# Underwater_vehicle-V3_0.net
KiCad netlist of a schematic drawn in Altium Designer
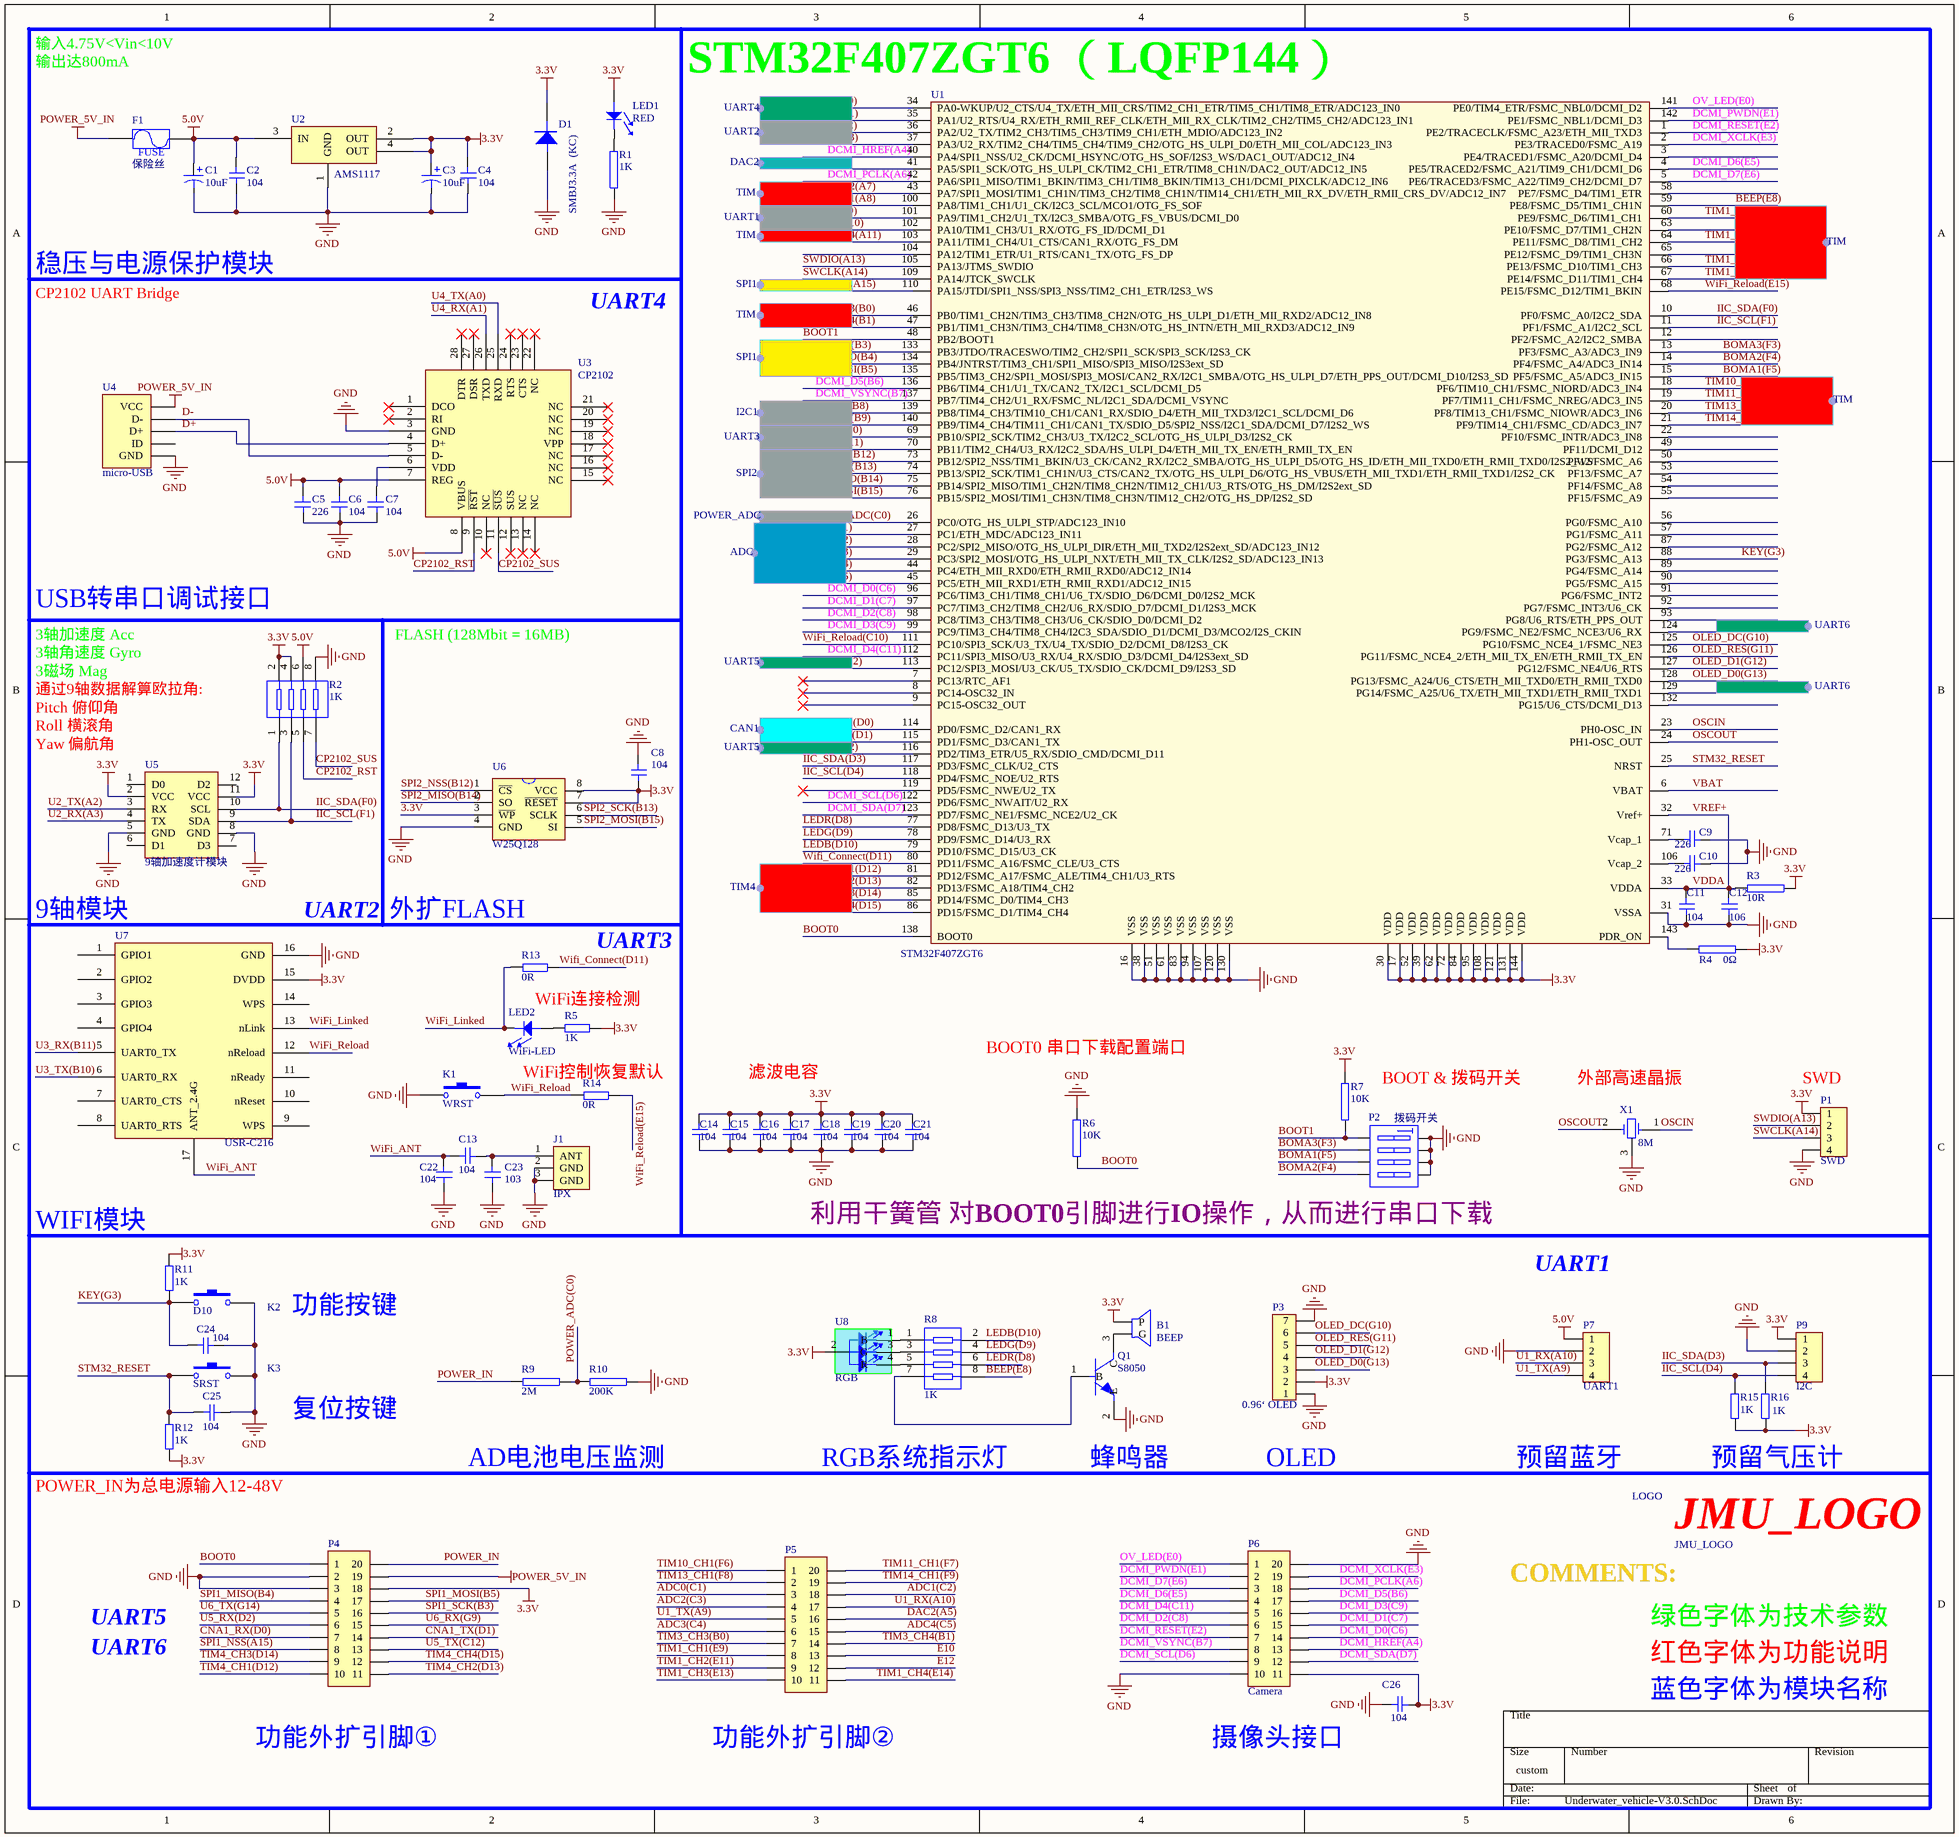
[diagram p0: Underwater_vehicle-V3.0.SchDoc]

(export (version "E")
  (design (tool "Eeschema 10.0.6"))
  (components
    (comp (ref "B1") (value "BEEP") (footprint "BUZZER") (libsource (lib "EXPLORER") (part "BEEP")))
    (comp (ref "C1")
      (value "10uF")
      (footprint "TAJ-A")
      (description "极性贴片电容")
      (libsource (lib "集大电协1.1.0") (part "Pol Cap"))
    )
    (comp (ref "C2")
      (value "104")
      (footprint "0805C")
      (description "无极贴片电容")
      (libsource (lib "集大电协1.1.0") (part "Cap1"))
    )
    (comp (ref "C3")
      (value "10uF")
      (footprint "TAJ-A")
      (description "极性贴片电容")
      (libsource (lib "集大电协1.1.0") (part "Pol Cap"))
    )
    (comp (ref "C4")
      (value "104")
      (footprint "0805C")
      (description "无极贴片电容")
      (libsource (lib "集大电协1.1.0") (part "Cap1"))
    )
    (comp (ref "C5")
      (value "226")
      (footprint "0805C")
      (description "无极贴片电容")
      (libsource (lib "集大电协1.1.0") (part "Cap1"))
    )
    (comp (ref "C6")
      (value "104")
      (footprint "0805C")
      (description "无极贴片电容")
      (libsource (lib "集大电协1.1.0") (part "Cap1"))
    )
    (comp (ref "C7")
      (value "104")
      (footprint "0805C")
      (description "无极贴片电容")
      (libsource (lib "集大电协1.1.0") (part "Cap1"))
    )
    (comp (ref "C8")
      (value "104")
      (footprint "0805C")
      (description "无极贴片电容")
      (libsource (lib "集大电协1.1.0") (part "Cap1"))
    )
    (comp (ref "C9") (value "226") (footprint "0805C") (libsource (lib "窝牛器件封装") (part "C1")))
    (comp (ref "C10") (value "226") (footprint "0805C") (libsource (lib "窝牛器件封装") (part "C1")))
    (comp (ref "C11") (value "104") (footprint "0805C") (libsource (lib "窝牛器件封装") (part "C1")))
    (comp (ref "C12") (value "106") (footprint "0805C") (libsource (lib "窝牛器件封装") (part "C1")))
    (comp (ref "C13")
      (value "104")
      (footprint "0805C")
      (description "无极贴片电容")
      (libsource (lib "集大电协1.1.2") (part "Cap1"))
    )
    (comp (ref "C14") (value "104") (footprint "0805C") (libsource (lib "窝牛器件封装") (part "C1")))
    (comp (ref "C15") (value "104") (footprint "0805C") (libsource (lib "窝牛器件封装") (part "C1")))
    (comp (ref "C16") (value "104") (footprint "0805C") (libsource (lib "窝牛器件封装") (part "C1")))
    (comp (ref "C17") (value "104") (footprint "0805C") (libsource (lib "窝牛器件封装") (part "C1")))
    (comp (ref "C18") (value "104") (footprint "0805C") (libsource (lib "窝牛器件封装") (part "C1")))
    (comp (ref "C19") (value "104") (footprint "0805C") (libsource (lib "窝牛器件封装") (part "C1")))
    (comp (ref "C20") (value "104") (footprint "0805C") (libsource (lib "窝牛器件封装") (part "C1")))
    (comp (ref "C21") (value "104") (footprint "0805C") (libsource (lib "窝牛器件封装") (part "C1")))
    (comp (ref "C22")
      (value "104")
      (footprint "0805C")
      (description "无极贴片电容")
      (libsource (lib "集大电协1.1.2") (part "Cap1"))
    )
    (comp (ref "C23")
      (value "103")
      (footprint "0805C")
      (description "无极贴片电容")
      (libsource (lib "集大电协1.1.2") (part "Cap1"))
    )
    (comp (ref "C24") (value "104") (footprint "0805C") (libsource (lib "窝牛器件封装") (part "C1")))
    (comp (ref "C25") (value "104") (footprint "0805C") (libsource (lib "窝牛器件封装") (part "C1")))
    (comp (ref "C26")
      (value "104")
      (footprint "0805C")
      (description "无极贴片电容")
      (libsource (lib "集大电协1.1.5") (part "Cap1"))
    )
    (comp (ref "D1")
      (value "SMBJ3.3A  (KC)")
      (footprint "SMBJ")
      (description "二极管")
      (libsource (lib "集大电协1.1.0") (part "Diode"))
    )
    (comp (ref "F1") (value "保险丝") (footprint "1812") (libsource (lib "集大电协1.1.2") (part "Fuse")))
    (comp (ref "J1") (value "IPX") (footprint "IPX天线底座") (libsource (lib "集大电协1.1.2") (part "IPX天线座")))
    (comp (ref "K1")
      (value "WRST")
      (footprint "贴片按键")
      (description "轻触开关")
      (libsource (lib "集大电协1.1.2") (part "轻触按键"))
    )
    (comp (ref "K2") (value "D10") (footprint "贴片按键") (libsource (lib "窝牛器件封装") (part "Key(两脚贴片)")))
    (comp (ref "K3") (value "SRST") (footprint "贴片按键") (libsource (lib "窝牛器件封装") (part "Key(两脚贴片)")))
    (comp (ref "LED1")
      (value "RED")
      (footprint "0805LED(RED)")
      (description "发光二极管")
      (libsource (lib "集大电协1.1.2") (part "LED"))
    )
    (comp (ref "LED2")
      (value "WiFi-LED")
      (footprint "0805LED(GREEN)")
      (description "发光二极管")
      (libsource (lib "集大电协1.1.2") (part "LED"))
    )
    (comp (ref "LOGO")
      (value "JMU_LOGO")
      (footprint "JMU_LOGO(1.35cm)")
      (description "LOGO")
      (libsource (lib "集大电协1.1.5") (part "JMU_LOGO"))
    )
    (comp (ref "P1")
      (value "SWD")
      (footprint "Header 4")
      (description "排针")
      (libsource (lib "集大电协1.1.0") (part "Header 4"))
    )
    (comp (ref "P2")
      (value "拨码开关")
      (footprint "拨码开关(4位贴片)")
      (description "4位拨码开关")
      (libsource (lib "集大电协1.1.2") (part "拨码开关4"))
    )
    (comp (ref "P3")
      (value "0.96‘ OLED")
      (footprint "Header 7")
      (description "排针")
      (libsource (lib "集大电协1.1.5") (part "Header 7"))
    )
    (comp (ref "P4") (value "~") (footprint "Header 10X2") (libsource (lib "集大电协1.1.2") (part "Header 10X2")))
    (comp (ref "P5") (value "~") (footprint "Header 10X2") (libsource (lib "集大电协1.1.2") (part "Header 10X2")))
    (comp (ref "P6")
      (value "Camera")
      (footprint "Header 10X2")
      (libsource (lib "集大电协1.1.2") (part "Header 10X2"))
    )
    (comp (ref "P7")
      (value "UART1")
      (footprint "Header 4(排母)")
      (description "排针")
      (libsource (lib "集大电协1.1.5") (part "Header 4"))
    )
    (comp (ref "P9")
      (value "I2C")
      (footprint "Header 4(排母)")
      (description "排针")
      (libsource (lib "集大电协1.1.5") (part "Header 4"))
    )
    (comp (ref "Q1")
      (value "S8050")
      (footprint "SOT-23")
      (description "NPN三极管")
      (libsource (lib "集大电协1.1.2") (part "NPN"))
    )
    (comp (ref "R1") (value "1K") (footprint "0805R") (libsource (lib "窝牛器件封装") (part "R1")))
    (comp (ref "R2")
      (value "1K")
      (footprint "排阻(4位贴片)")
      (description "排阻")
      (libsource (lib "集大电协1.1.2") (part "Res-4"))
    )
    (comp (ref "R3") (value "10R") (footprint "0805R") (libsource (lib "窝牛器件封装") (part "R1")))
    (comp (ref "R4") (value "0Ω") (footprint "0805R") (libsource (lib "窝牛器件封装") (part "R1")))
    (comp (ref "R5")
      (value "1K")
      (footprint "0805R")
      (description "电阻")
      (libsource (lib "集大电协1.1.2") (part "Res"))
    )
    (comp (ref "R6") (value "10K") (footprint "0805R") (libsource (lib "窝牛器件封装") (part "R1")))
    (comp (ref "R7") (value "10K") (footprint "0805R") (libsource (lib "窝牛器件封装") (part "R1")))
    (comp (ref "R8")
      (value "1K")
      (footprint "排阻(4位贴片)")
      (description "排阻")
      (libsource (lib "集大电协1.1.2") (part "Res-4"))
    )
    (comp (ref "R9") (value "2M") (footprint "0805R") (libsource (lib "窝牛器件封装") (part "R1")))
    (comp (ref "R10") (value "200K") (footprint "0805R") (libsource (lib "窝牛器件封装") (part "R1")))
    (comp (ref "R11")
      (value "1K")
      (footprint "0805R")
      (description "电阻")
      (libsource (lib "集大电协1.1.5") (part "Res"))
    )
    (comp (ref "R12")
      (value "1K")
      (footprint "0805R")
      (description "电阻")
      (libsource (lib "集大电协1.1.5") (part "Res"))
    )
    (comp (ref "R13")
      (value "0R")
      (footprint "0805R")
      (description "电阻")
      (libsource (lib "集大电协1.1.5") (part "Res"))
    )
    (comp (ref "R14")
      (value "0R")
      (footprint "0805R")
      (description "电阻")
      (libsource (lib "集大电协1.1.5") (part "Res"))
    )
    (comp (ref "R15")
      (value "1K")
      (footprint "0805R")
      (description "电阻")
      (libsource (lib "集大电协1.2") (part "Res"))
    )
    (comp (ref "R16")
      (value "1K")
      (footprint "0805R")
      (description "电阻")
      (libsource (lib "集大电协1.2") (part "Res"))
    )
    (comp (ref "U1")
      (value "STM32F407ZGT6")
      (footprint "LQFP-144")
      (libsource (lib "窝牛器件封装") (part "STM32F407ZET6"))
    )
    (comp (ref "U2")
      (value "AMS1117")
      (footprint "SOT-223")
      (description "电源芯片")
      (libsource (lib "集大电协1.1.0") (part "AMS1117-3.3V/5.0V"))
    )
    (comp (ref "U3")
      (value "CP2102")
      (footprint "QFN-28")
      (description "USB转串口芯片")
      (libsource (lib "集大电协1.1.0") (part "CP2102"))
    )
    (comp (ref "U4")
      (value "micro-USB")
      (footprint "Micro-USB (兼容牛角)")
      (description "USB接口")
      (libsource (lib "集大电协1.1.2") (part "micro-USB"))
    )
    (comp (ref "U5") (value "9轴加速度计模块") (footprint "9轴加速度计") (libsource (lib "窝牛器件封装") (part "9轴加速度计")))
    (comp (ref "U6")
      (value "W25Q128")
      (footprint "SOW-8")
      (description "FLASH芯片")
      (libsource (lib "集大电协1.1.0") (part "W25Q128"))
    )
    (comp (ref "U7")
      (value "USR-C216")
      (footprint "USR-C216")
      (libsource (lib "集大电协1.1.2") (part "USR-C216"))
    )
    (comp (ref "U8") (value "RGB") (footprint "RGB-3528") (libsource (lib "集大电协1.1.2") (part "RGB")))
    (comp (ref "X1") (value "8M") (footprint "三脚贴片8M晶振") (libsource (lib "集大电协1.1.2") (part "XTAL三脚贴片晶振")))
  )
  (nets
    (net (code "2") (name "/ADC0(C1)") (class "Default")
      (node (ref "P5") (pin "3") (pinfunction "3_3") (pintype "passive"))
      (node (ref "U1") (pin "27") (pinfunction "PC1/ETH_MDC/ADC123_IN11_27") (pintype "passive"))
    )
    (net (code "3") (name "/ADC1(C2)") (class "Default")
      (node (ref "P5") (pin "18") (pinfunction "18_18") (pintype "passive"))
      (node (ref "U1") (pin "28") (pinfunction "PC2/SPI2_MISO/OTG_HS_ULPI_DIR/ETH_MII_TXD2/I2S2ext_SD/ADC123_IN12_28") (pintype "passive"))
    )
    (net (code "4") (name "/ADC2(C3)") (class "Default")
      (node (ref "P5") (pin "4") (pinfunction "4_4") (pintype "passive"))
      (node (ref "U1") (pin "29") (pinfunction "PC3/SPI2_MOSI/OTG_HS_ULPI_NXT/ETH_MII_TX_CLK/I2S2_SD/ADC123_IN13_29") (pintype "passive"))
    )
    (net (code "5") (name "/ADC3(C4)") (class "Default")
      (node (ref "P5") (pin "6") (pinfunction "6_6") (pintype "passive"))
      (node (ref "U1") (pin "44") (pinfunction "PC4/ETH_MII_RXD0/ETH_RMII_RXD0/ADC12_IN14_44") (pintype "passive"))
    )
    (net (code "6") (name "/ADC4(C5)") (class "Default")
      (node (ref "P5") (pin "15") (pinfunction "15_15") (pintype "passive"))
      (node (ref "U1") (pin "45") (pinfunction "PC5/ETH_MII_RXD1/ETH_RMII_RXD1/ADC12_IN15_45") (pintype "passive"))
    )
    (net (code "7") (name "/BEEP(E8)") (class "Default")
      (node (ref "R8") (pin "8") (pinfunction "8_8") (pintype "passive"))
      (node (ref "U1") (pin "59") (pinfunction "PE8/FSMC_D5/TIM1_CH1N_59") (pintype "passive"))
    )
    (net (code "8") (name "/BOMA1(F5)") (class "Default")
      (node (ref "P2") (pin "3") (pinfunction "A3_3") (pintype "passive"))
      (node (ref "U1") (pin "15") (pinfunction "PF5/FSMC_A5/ADC3_IN15_15") (pintype "passive"))
    )
    (net (code "9") (name "/BOMA2(F4)") (class "Default")
      (node (ref "P2") (pin "4") (pinfunction "A4_4") (pintype "passive"))
      (node (ref "U1") (pin "14") (pinfunction "PF4/FSMC_A4/ADC3_IN14_14") (pintype "passive"))
    )
    (net (code "10") (name "/BOMA3(F3)") (class "Default")
      (node (ref "P2") (pin "2") (pinfunction "A2_2") (pintype "passive"))
      (node (ref "U1") (pin "13") (pinfunction "PF3/FSMC_A3/ADC3_IN9_13") (pintype "passive"))
    )
    (net (code "11") (name "/BOOT0") (class "Default")
      (node (ref "P4") (pin "1") (pinfunction "1_1") (pintype "passive"))
      (node (ref "R6") (pin "1") (pinfunction "1_1") (pintype "passive"))
      (node (ref "U1") (pin "138") (pinfunction "BOOT0_138") (pintype "passive"))
    )
    (net (code "12") (name "/BOOT1") (class "Default")
      (node (ref "P2") (pin "1") (pinfunction "A1_1") (pintype "passive"))
      (node (ref "R7") (pin "1") (pinfunction "1_1") (pintype "passive"))
      (node (ref "U1") (pin "48") (pinfunction "PB2/BOOT1_48") (pintype "passive"))
    )
    (net (code "13") (name "/CNA1_RX(D0)") (class "Default")
      (node (ref "P4") (pin "7") (pinfunction "7_7") (pintype "passive"))
      (node (ref "U1") (pin "114") (pinfunction "PD0/FSMC_D2/CAN1_RX_114") (pintype "passive"))
    )
    (net (code "14") (name "/CNA1_TX(D1)") (class "Default")
      (node (ref "P4") (pin "14") (pinfunction "14_14") (pintype "passive"))
      (node (ref "U1") (pin "115") (pinfunction "PD1/FSMC_D3/CAN1_TX_115") (pintype "passive"))
    )
    (net (code "15") (name "/CP2102_RST") (class "Default")
      (node (ref "R2") (pin "5") (pinfunction "5_5") (pintype "passive"))
      (node (ref "U3") (pin "9") (pinfunction "~{RST}_9") (pintype "passive"))
    )
    (net (code "16") (name "/CP2102_SUS") (class "Default")
      (node (ref "R2") (pin "7") (pinfunction "7_7") (pintype "passive"))
      (node (ref "U3") (pin "11") (pinfunction "~{SUS}_11") (pintype "passive"))
    )
    (net (code "17") (name "/D+") (class "Default")
      (node (ref "U3") (pin "4") (pinfunction "D+_4") (pintype "passive"))
      (node (ref "U4") (pin "3") (pinfunction "D+_3") (pintype "power_in"))
    )
    (net (code "18") (name "/D-") (class "Default")
      (node (ref "U3") (pin "5") (pinfunction "D-_5") (pintype "passive"))
      (node (ref "U4") (pin "2") (pinfunction "D-_2") (pintype "power_in"))
    )
    (net (code "19") (name "/DAC2(A5)") (class "Default")
      (node (ref "P5") (pin "16") (pinfunction "16_16") (pintype "passive"))
      (node (ref "U1") (pin "41") (pinfunction "PA5/SPI1_SCK/OTG_HS_ULPI_CK/TIM2_CH1_ETR/TIM8_CH1N/DAC2_OUT/ADC12_IN5_41") (pintype "passive"))
    )
    (net (code "20") (name "/DCMI_D0(C6)") (class "Default")
      (node (ref "P6") (pin "14") (pinfunction "14_14") (pintype "passive"))
      (node (ref "U1") (pin "96") (pinfunction "PC6/TIM3_CH1/TIM8_CH1/U6_TX/SDIO_D6/DCMI_D0/I2S2_MCK_96") (pintype "passive"))
    )
    (net (code "21") (name "/DCMI_D1(C7)") (class "Default")
      (node (ref "P6") (pin "15") (pinfunction "15_15") (pintype "passive"))
      (node (ref "U1") (pin "97") (pinfunction "PC7/TIM3_CH2/TIM8_CH2/U6_RX/SDIO_D7/DCMI_D1/I2S3_MCK_97") (pintype "passive"))
    )
    (net (code "22") (name "/DCMI_D2(C8)") (class "Default")
      (node (ref "P6") (pin "6") (pinfunction "6_6") (pintype "passive"))
      (node (ref "U1") (pin "98") (pinfunction "PC8/TIM3_CH3/TIM8_CH3/U6_CK/SDIO_D0/DCMI_D2_98") (pintype "passive"))
    )
    (net (code "23") (name "/DCMI_D3(C9)") (class "Default")
      (node (ref "P6") (pin "16") (pinfunction "16_16") (pintype "passive"))
      (node (ref "U1") (pin "99") (pinfunction "PC9/TIM3_CH4/TIM8_CH4/I2C3_SDA/SDIO_D1/DCMI_D3/MCO2/I2S_CKIN_99") (pintype "passive"))
    )
    (net (code "24") (name "/DCMI_D4(C11)") (class "Default")
      (node (ref "P6") (pin "5") (pinfunction "5_5") (pintype "passive"))
      (node (ref "U1") (pin "112") (pinfunction "PC11/SPI3_MISO/U3_RX/U4_RX/SDIO_D3/DCMI_D4/I2S3ext_SD_112") (pintype "passive"))
    )
    (net (code "25") (name "/DCMI_D5(B6)") (class "Default")
      (node (ref "P6") (pin "17") (pinfunction "17_17") (pintype "passive"))
      (node (ref "U1") (pin "136") (pinfunction "PB6/TIM4_CH1/U1_TX/CAN2_TX/I2C1_SCL/DCMI_D5_136") (pintype "passive"))
    )
    (net (code "26") (name "/DCMI_D6(E5)") (class "Default")
      (node (ref "P6") (pin "4") (pinfunction "4_4") (pintype "passive"))
      (node (ref "U1") (pin "4") (pinfunction "PE5/TRACED2/FSMC_A21/TIM9_CH1/DCMI_D6_4") (pintype "passive"))
    )
    (net (code "27") (name "/DCMI_D7(E6)") (class "Default")
      (node (ref "P6") (pin "3") (pinfunction "3_3") (pintype "passive"))
      (node (ref "U1") (pin "5") (pinfunction "PE6/TRACED3/FSMC_A22/TIM9_CH2/DCMI_D7_5") (pintype "passive"))
    )
    (net (code "28") (name "/DCMI_HREF(A4)") (class "Default")
      (node (ref "P6") (pin "13") (pinfunction "13_13") (pintype "passive"))
      (node (ref "U1") (pin "40") (pinfunction "PA4/SPI1_NSS/U2_CK/DCMI_HSYNC/OTG_HS_SOF/I2S3_WS/DAC1_OUT/ADC12_IN4_40") (pintype "passive"))
    )
    (net (code "29") (name "/DCMI_PCLK(A6)") (class "Default")
      (node (ref "P6") (pin "18") (pinfunction "18_18") (pintype "passive"))
      (node (ref "U1") (pin "42") (pinfunction "PA6/SPI1_MISO/TIM1_BKIN/TIM3_CH1/TIM8_BKIN/TIM13_CH1/DCMI_PIXCLK/ADC12_IN6_42") (pintype "passive"))
    )
    (net (code "30") (name "/DCMI_PWDN(E1)") (class "Default")
      (node (ref "P6") (pin "2") (pinfunction "2_2") (pintype "passive"))
      (node (ref "U1") (pin "142") (pinfunction "PE1/FSMC_NBL1/DCMI_D3_142") (pintype "passive"))
    )
    (net (code "31") (name "/DCMI_RESET(E2)") (class "Default")
      (node (ref "P6") (pin "7") (pinfunction "7_7") (pintype "passive"))
      (node (ref "U1") (pin "1") (pinfunction "PE2/TRACECLK/FSMC_A23/ETH_MII_TXD3_1") (pintype "passive"))
    )
    (net (code "32") (name "/DCMI_SCL(D6)") (class "Default")
      (node (ref "P6") (pin "9") (pinfunction "9_9") (pintype "passive"))
      (node (ref "U1") (pin "122") (pinfunction "PD6/FSMC_NWAIT/U2_RX_122") (pintype "passive"))
    )
    (net (code "33") (name "/DCMI_SDA(D7)") (class "Default")
      (node (ref "P6") (pin "12") (pinfunction "12_12") (pintype "passive"))
      (node (ref "U1") (pin "123") (pinfunction "PD7/FSMC_NE1/FSMC_NCE2/U2_CK_123") (pintype "passive"))
    )
    (net (code "34") (name "/DCMI_VSYNC(B7)") (class "Default")
      (node (ref "P6") (pin "8") (pinfunction "8_8") (pintype "passive"))
      (node (ref "U1") (pin "137") (pinfunction "PB7/TIM4_CH2/U1_RX/FSMC_NL/I2C1_SDA/DCMI_VSYNC_137") (pintype "passive"))
    )
    (net (code "35") (name "/DCMI_XCLK(E3)") (class "Default")
      (node (ref "P6") (pin "19") (pinfunction "19_19") (pintype "passive"))
      (node (ref "U1") (pin "2") (pinfunction "PE3/TRACED0/FSMC_A19_2") (pintype "passive"))
    )
    (net (code "36") (name "/E10") (class "Default")
      (node (ref "P5") (pin "13") (pinfunction "13_13") (pintype "passive"))
      (node (ref "U1") (pin "63") (pinfunction "PE10/FSMC_D7/TIM1_CH2N_63") (pintype "passive"))
    )
    (net (code "37") (name "/E12") (class "Default")
      (node (ref "P5") (pin "12") (pinfunction "12_12") (pintype "passive"))
      (node (ref "U1") (pin "65") (pinfunction "PE12/FSMC_D9/TIM1_CH3N_65") (pintype "passive"))
    )
    (net (code "38") (name "/IIC1_SCL(B8)") (class "Default")
      (node (ref "U1") (pin "139") (pinfunction "PB8/TIM4_CH3/TIM10_CH1/CAN1_RX/SDIO_D4/ETH_MII_TXD3/I2C1_SCL/DCMI_D6_139") (pintype "passive"))
    )
    (net (code "39") (name "/IIC1_SDA(B9)") (class "Default")
      (node (ref "U1") (pin "140") (pinfunction "PB9/TIM4_CH4/TIM11_CH1/CAN1_TX/SDIO_D5/SPI2_NSS/I2C1_SDA/DCMI_D7/I2S2_WS_140") (pintype "passive"))
    )
    (net (code "40") (name "/IIC_SCL(D4)") (class "Default")
      (node (ref "P9") (pin "4") (pinfunction "4_4") (pintype "passive"))
      (node (ref "R15") (pin "2") (pinfunction "2_2") (pintype "passive"))
      (node (ref "U1") (pin "118") (pinfunction "PD4/FSMC_NOE/U2_RTS_118") (pintype "passive"))
    )
    (net (code "41") (name "/IIC_SCL(F1)") (class "Default")
      (node (ref "R2") (pin "3") (pinfunction "3_3") (pintype "passive"))
      (node (ref "U1") (pin "11") (pinfunction "PF1/FSMC_A1/I2C2_SCL_11") (pintype "passive"))
      (node (ref "U5") (pin "9") (pinfunction "SDA_9") (pintype "passive"))
    )
    (net (code "42") (name "/IIC_SDA(D3)") (class "Default")
      (node (ref "P9") (pin "3") (pinfunction "3_3") (pintype "passive"))
      (node (ref "R16") (pin "2") (pinfunction "2_2") (pintype "passive"))
      (node (ref "U1") (pin "117") (pinfunction "PD3/FSMC_CLK/U2_CTS_117") (pintype "passive"))
    )
    (net (code "43") (name "/IIC_SDA(F0)") (class "Default")
      (node (ref "R2") (pin "1") (pinfunction "1_1") (pintype "passive"))
      (node (ref "U1") (pin "10") (pinfunction "PF0/FSMC_A0/I2C2_SDA_10") (pintype "passive"))
      (node (ref "U5") (pin "10") (pinfunction "SCL_10") (pintype "passive"))
    )
    (net (code "44") (name "/KEY(G3)") (class "Default")
      (node (ref "C24") (pin "1") (pinfunction "1_1") (pintype "passive"))
      (node (ref "K2") (pin "1") (pinfunction "1_1") (pintype "passive"))
      (node (ref "R11") (pin "1") (pinfunction "1_1") (pintype "passive"))
      (node (ref "U1") (pin "88") (pinfunction "PG3/FSMC_A13_88") (pintype "passive"))
    )
    (net (code "45") (name "/LEDB(D10)") (class "Default")
      (node (ref "R8") (pin "2") (pinfunction "2_2") (pintype "passive"))
      (node (ref "U1") (pin "79") (pinfunction "PD10/FSMC_D15/U3_CK_79") (pintype "passive"))
    )
    (net (code "46") (name "/LEDG(D9)") (class "Default")
      (node (ref "R8") (pin "4") (pinfunction "4_4") (pintype "passive"))
      (node (ref "U1") (pin "78") (pinfunction "PD9/FSMC_D14/U3_RX_78") (pintype "passive"))
    )
    (net (code "47") (name "/LEDR(D8)") (class "Default")
      (node (ref "R8") (pin "6") (pinfunction "6_6") (pintype "passive"))
      (node (ref "U1") (pin "77") (pinfunction "PD8/FSMC_D13/U3_TX_77") (pintype "passive"))
    )
    (net (code "48") (name "/OLED_D0(G13)") (class "Default")
      (node (ref "P3") (pin "3") (pinfunction "3_3") (pintype "passive"))
      (node (ref "U1") (pin "128") (pinfunction "PG13/FSMC_A24/U6_CTS/ETH_MII_TXD0/ETH_RMII_TXD0_128") (pintype "passive"))
    )
    (net (code "49") (name "/OLED_D1(G12)") (class "Default")
      (node (ref "P3") (pin "4") (pinfunction "4_4") (pintype "passive"))
      (node (ref "U1") (pin "127") (pinfunction "PG12/FSMC_NE4/U6_RTS_127") (pintype "passive"))
    )
    (net (code "50") (name "/OLED_DC(G10)") (class "Default")
      (node (ref "P3") (pin "6") (pinfunction "6_6") (pintype "passive"))
      (node (ref "U1") (pin "125") (pinfunction "PG10/FSMC_NCE4_1/FSMC_NE3_125") (pintype "passive"))
    )
    (net (code "51") (name "/OLED_RES(G11)") (class "Default")
      (node (ref "P3") (pin "5") (pinfunction "5_5") (pintype "passive"))
      (node (ref "U1") (pin "126") (pinfunction "PG11/FSMC_NCE4_2/ETH_MII_TX_EN/ETH_RMII_TX_EN_126") (pintype "passive"))
    )
    (net (code "52") (name "/OSCIN") (class "Default")
      (node (ref "U1") (pin "23") (pinfunction "PH0-OSC_IN_23") (pintype "passive"))
      (node (ref "X1") (pin "1") (pinfunction "1_1") (pintype "passive"))
    )
    (net (code "53") (name "/OSCOUT") (class "Default")
      (node (ref "U1") (pin "24") (pinfunction "PH1-OSC_OUT_24") (pintype "passive"))
      (node (ref "X1") (pin "2") (pinfunction "2_2") (pintype "passive"))
    )
    (net (code "54") (name "/OV_LED(E0)") (class "Default")
      (node (ref "P6") (pin "1") (pinfunction "1_1") (pintype "passive"))
      (node (ref "U1") (pin "141") (pinfunction "PE0/TIM4_ETR/FSMC_NBL0/DCMI_D2_141") (pintype "passive"))
    )
    (net (code "55") (name "/POWER_ADC(C0)") (class "Default")
      (node (ref "R10") (pin "1") (pinfunction "1_1") (pintype "passive"))
      (node (ref "R9") (pin "2") (pinfunction "2_2") (pintype "passive"))
      (node (ref "U1") (pin "26") (pinfunction "PC0/OTG_HS_ULPI_STP/ADC123_IN10_26") (pintype "passive"))
    )
    (net (code "56") (name "/POWER_IN") (class "Default")
      (node (ref "P4") (pin "20") (pinfunction "20_20") (pintype "passive"))
      (node (ref "R9") (pin "1") (pinfunction "1_1") (pintype "passive"))
    )
    (net (code "57") (name "/SPI1_MISO(B4)") (class "Default")
      (node (ref "P4") (pin "4") (pinfunction "4_4") (pintype "passive"))
      (node (ref "U1") (pin "134") (pinfunction "PB4/JNTRST/TIM3_CH1/SPI1_MISO/SPI3_MISO/I2S3ext_SD_134") (pintype "passive"))
    )
    (net (code "58") (name "/SPI1_MOSI(B5)") (class "Default")
      (node (ref "P4") (pin "17") (pinfunction "17_17") (pintype "passive"))
      (node (ref "U1") (pin "135") (pinfunction "PB5/TIM3_CH2/SPI1_MOSI/SPI3_MOSI/CAN2_RX/I2C1_SMBA/OTG_HS_ULPI_D7/ETH_PPS_OUT/DCMI_D10/I2S3_SD_135") (pintype "passive"))
    )
    (net (code "59") (name "/SPI1_NSS(A15)") (class "Default")
      (node (ref "P4") (pin "8") (pinfunction "8_8") (pintype "passive"))
      (node (ref "U1") (pin "110") (pinfunction "PA15/JTDI/SPI1_NSS/SPI3_NSS/TIM2_CH1_ETR/I2S3_WS_110") (pintype "passive"))
    )
    (net (code "60") (name "/SPI1_SCK(B3)") (class "Default")
      (node (ref "P4") (pin "16") (pinfunction "16_16") (pintype "passive"))
      (node (ref "U1") (pin "133") (pinfunction "PB3/JTDO/TRACESWO/TIM2_CH2/SPI1_SCK/SPI3_SCK/I2S3_CK_133") (pintype "passive"))
    )
    (net (code "61") (name "/SPI2_MISO(B14)") (class "Default")
      (node (ref "U1") (pin "75") (pinfunction "PB14/SPI2_MISO/TIM1_CH2N/TIM8_CH2N/TIM12_CH1/U3_RTS/OTG_HS_DM/I2S2ext_SD_75") (pintype "passive"))
      (node (ref "U6") (pin "2") (pinfunction "SO_2") (pintype "passive"))
    )
    (net (code "62") (name "/SPI2_MOSI(B15)") (class "Default")
      (node (ref "U1") (pin "76") (pinfunction "PB15/SPI2_MOSI/TIM1_CH3N/TIM8_CH3N/TIM12_CH2/OTG_HS_DP/I2S2_SD_76") (pintype "passive"))
      (node (ref "U6") (pin "5") (pinfunction "SI_5") (pintype "passive"))
    )
    (net (code "63") (name "/SPI2_NSS(B12)") (class "Default")
      (node (ref "U1") (pin "73") (pinfunction "PB12/SPI2_NSS/TIM1_BKIN/U3_CK/CAN2_RX/I2C2_SMBA/OTG_HS_ULPI_D5/OTG_HS_ID/ETH_MII_TXD0/ETH_RMII_TXD0/I2S2_WS_73") (pintype "passive"))
      (node (ref "U6") (pin "1") (pinfunction "~{CS}_1") (pintype "passive"))
    )
    (net (code "64") (name "/SPI2_SCK(B13)") (class "Default")
      (node (ref "U1") (pin "74") (pinfunction "PB13/SPI2_SCK/TIM1_CH1N/U3_CTS/CAN2_TX/OTG_HS_ULPI_D6/OTG_HS_VBUS/ETH_MII_TXD1/ETH_RMII_TXD1/I2S2_CK_74") (pintype "passive"))
      (node (ref "U6") (pin "6") (pinfunction "SCLK_6") (pintype "passive"))
    )
    (net (code "65") (name "/STM32_RESET") (class "Default")
      (node (ref "C25") (pin "1") (pinfunction "1_1") (pintype "passive"))
      (node (ref "K3") (pin "1") (pinfunction "1_1") (pintype "passive"))
      (node (ref "R12") (pin "2") (pinfunction "2_2") (pintype "passive"))
      (node (ref "U1") (pin "25") (pinfunction "NRST_25") (pintype "passive"))
    )
    (net (code "66") (name "/SWCLK(A14)") (class "Default")
      (node (ref "P1") (pin "3") (pinfunction "3_3") (pintype "passive"))
      (node (ref "U1") (pin "109") (pinfunction "PA14/JTCK_SWCLK_109") (pintype "passive"))
    )
    (net (code "67") (name "/SWDIO(A13)") (class "Default")
      (node (ref "P1") (pin "2") (pinfunction "2_2") (pintype "passive"))
      (node (ref "U1") (pin "105") (pinfunction "PA13/JTMS_SWDIO_105") (pintype "passive"))
    )
    (net (code "68") (name "/TIM1_CH1(A8)") (class "Default")
      (node (ref "U1") (pin "100") (pinfunction "PA8/TIM1_CH1/U1_CK/I2C3_SCL/MCO1/OTG_FS_SOF_100") (pintype "passive"))
    )
    (net (code "69") (name "/TIM1_CH1(E9)") (class "Default")
      (node (ref "P5") (pin "8") (pinfunction "8_8") (pintype "passive"))
      (node (ref "U1") (pin "60") (pinfunction "PE9/FSMC_D6/TIM1_CH1_60") (pintype "passive"))
    )
    (net (code "70") (name "/TIM1_CH2(E11)") (class "Default")
      (node (ref "P5") (pin "9") (pinfunction "9_9") (pintype "passive"))
      (node (ref "U1") (pin "64") (pinfunction "PE11/FSMC_D8/TIM1_CH2_64") (pintype "passive"))
    )
    (net (code "71") (name "/TIM1_CH3(E13)") (class "Default")
      (node (ref "P5") (pin "10") (pinfunction "10_10") (pintype "passive"))
      (node (ref "U1") (pin "66") (pinfunction "PE13/FSMC_D10/TIM1_CH3_66") (pintype "passive"))
    )
    (net (code "72") (name "/TIM1_CH4(A11)") (class "Default")
      (node (ref "U1") (pin "103") (pinfunction "PA11/TIM1_CH4/U1_CTS/CAN1_RX/OTG_FS_DM_103") (pintype "passive"))
    )
    (net (code "73") (name "/TIM1_CH4(E14)") (class "Default")
      (node (ref "P5") (pin "11") (pinfunction "11_11") (pintype "passive"))
      (node (ref "U1") (pin "67") (pinfunction "PE14/FSMC_D11/TIM1_CH4_67") (pintype "passive"))
    )
    (net (code "74") (name "/TIM3_CH2(A7)") (class "Default")
      (node (ref "U1") (pin "43") (pinfunction "PA7/SPI1_MOSI/TIM1_CH1N/TIM3_CH2/TIM8_CH1N/TIM14_CH1/ETH_MII_RX_DV/ETH_RMII_CRS_DV/ADC12_IN7_43") (pintype "passive"))
    )
    (net (code "75") (name "/TIM3_CH3(B0)") (class "Default")
      (node (ref "P5") (pin "7") (pinfunction "7_7") (pintype "passive"))
      (node (ref "U1") (pin "46") (pinfunction "PB0/TIM1_CH2N/TIM3_CH3/TIM8_CH2N/OTG_HS_ULPI_D1/ETH_MII_RXD2/ADC12_IN8_46") (pintype "passive"))
    )
    (net (code "76") (name "/TIM3_CH4(B1)") (class "Default")
      (node (ref "P5") (pin "14") (pinfunction "14_14") (pintype "passive"))
      (node (ref "U1") (pin "47") (pinfunction "PB1/TIM1_CH3N/TIM3_CH4/TIM8_CH3N/OTG_HS_INTN/ETH_MII_RXD3/ADC12_IN9_47") (pintype "passive"))
    )
    (net (code "77") (name "/TIM4_CH1(D12)") (class "Default")
      (node (ref "P4") (pin "10") (pinfunction "10_10") (pintype "passive"))
      (node (ref "U1") (pin "81") (pinfunction "PD12/FSMC_A17/FSMC_ALE/TIM4_CH1/U3_RTS_81") (pintype "passive"))
    )
    (net (code "78") (name "/TIM4_CH2(D13)") (class "Default")
      (node (ref "P4") (pin "11") (pinfunction "11_11") (pintype "passive"))
      (node (ref "U1") (pin "82") (pinfunction "PD13/FSMC_A18/TIM4_CH2_82") (pintype "passive"))
    )
    (net (code "79") (name "/TIM4_CH3(D14)") (class "Default")
      (node (ref "P4") (pin "9") (pinfunction "9_9") (pintype "passive"))
      (node (ref "U1") (pin "85") (pinfunction "PD14/FSMC_D0/TIM4_CH3_85") (pintype "passive"))
    )
    (net (code "80") (name "/TIM4_CH4(D15)") (class "Default")
      (node (ref "P4") (pin "12") (pinfunction "12_12") (pintype "passive"))
      (node (ref "U1") (pin "86") (pinfunction "PD15/FSMC_D1/TIM4_CH4_86") (pintype "passive"))
    )
    (net (code "81") (name "/TIM10_CH1(F6)") (class "Default")
      (node (ref "P5") (pin "1") (pinfunction "1_1") (pintype "passive"))
      (node (ref "U1") (pin "18") (pinfunction "PF6/TIM10_CH1/FSMC_NIORD/ADC3_IN4_18") (pintype "passive"))
    )
    (net (code "82") (name "/TIM11_CH1(F7)") (class "Default")
      (node (ref "P5") (pin "20") (pinfunction "20_20") (pintype "passive"))
      (node (ref "U1") (pin "19") (pinfunction "PF7/TIM11_CH1/FSMC_NREG/ADC3_IN5_19") (pintype "passive"))
    )
    (net (code "83") (name "/TIM13_CH1(F8)") (class "Default")
      (node (ref "P5") (pin "2") (pinfunction "2_2") (pintype "passive"))
      (node (ref "U1") (pin "20") (pinfunction "PF8/TIM13_CH1/FSMC_NIOWR/ADC3_IN6_20") (pintype "passive"))
    )
    (net (code "84") (name "/TIM14_CH1(F9)") (class "Default")
      (node (ref "P5") (pin "19") (pinfunction "19_19") (pintype "passive"))
      (node (ref "U1") (pin "21") (pinfunction "PF9/TIM14_CH1/FSMC_CD/ADC3_IN7_21") (pintype "passive"))
    )
    (net (code "85") (name "/U1_RX(A10)") (class "Default")
      (node (ref "P5") (pin "17") (pinfunction "17_17") (pintype "passive"))
      (node (ref "P7") (pin "3") (pinfunction "3_3") (pintype "passive"))
      (node (ref "U1") (pin "102") (pinfunction "PA10/TIM1_CH3/U1_RX/OTG_FS_ID/DCMI_D1_102") (pintype "passive"))
    )
    (net (code "86") (name "/U1_TX(A9)") (class "Default")
      (node (ref "P5") (pin "5") (pinfunction "5_5") (pintype "passive"))
      (node (ref "P7") (pin "4") (pinfunction "4_4") (pintype "passive"))
      (node (ref "U1") (pin "101") (pinfunction "PA9/TIM1_CH2/U1_TX/I2C3_SMBA/OTG_FS_VBUS/DCMI_D0_101") (pintype "passive"))
    )
    (net (code "87") (name "/U2_RX(A3)") (class "Default")
      (node (ref "U1") (pin "37") (pinfunction "PA3/U2_RX/TIM2_CH4/TIM5_CH4/TIM9_CH2/OTG_HS_ULPI_D0/ETH_MII_COL/ADC123_IN3_37") (pintype "passive"))
      (node (ref "U5") (pin "4") (pinfunction "TX_4") (pintype "passive"))
    )
    (net (code "88") (name "/U2_TX(A2)") (class "Default")
      (node (ref "U1") (pin "36") (pinfunction "PA2/U2_TX/TIM2_CH3/TIM5_CH3/TIM9_CH1/ETH_MDIO/ADC123_IN2_36") (pintype "passive"))
      (node (ref "U5") (pin "3") (pinfunction "RX_3") (pintype "passive"))
    )
    (net (code "89") (name "/U3_RX(B11)") (class "Default")
      (node (ref "U1") (pin "70") (pinfunction "PB11/TIM2_CH4/U3_RX/I2C2_SDA/HS_ULPI_D4/ETH_MII_TX_EN/ETH_RMII_TX_EN_70") (pintype "passive"))
      (node (ref "U7") (pin "5") (pinfunction "UART0_TX_5") (pintype "passive"))
    )
    (net (code "90") (name "/U3_TX(B10)") (class "Default")
      (node (ref "U1") (pin "69") (pinfunction "PB10/SPI2_SCK/TIM2_CH3/U3_TX/I2C2_SCL/OTG_HS_ULPI_D3/I2S2_CK_69") (pintype "passive"))
      (node (ref "U7") (pin "6") (pinfunction "UART0_RX_6") (pintype "passive"))
    )
    (net (code "91") (name "/U4_RX(A1)") (class "Default")
      (node (ref "U1") (pin "35") (pinfunction "PA1/U2_RTS/U4_RX/ETH_RMII_REF_CLK/ETH_MII_RX_CLK/TIM2_CH2/TIM5_CH2/ADC123_IN1_35") (pintype "passive"))
      (node (ref "U3") (pin "26") (pinfunction "TXD_26") (pintype "passive"))
    )
    (net (code "92") (name "/U4_TX(A0)") (class "Default")
      (node (ref "U1") (pin "34") (pinfunction "PA0-WKUP/U2_CTS/U4_TX/ETH_MII_CRS/TIM2_CH1_ETR/TIM5_CH1/TIM8_ETR/ADC123_IN0_34") (pintype "passive"))
      (node (ref "U3") (pin "25") (pinfunction "RXD_25") (pintype "passive"))
    )
    (net (code "93") (name "/U5_RX(D2)") (class "Default")
      (node (ref "P4") (pin "6") (pinfunction "6_6") (pintype "passive"))
      (node (ref "U1") (pin "116") (pinfunction "PD2/TIM3_ETR/U5_RX/SDIO_CMD/DCMI_D11_116") (pintype "passive"))
    )
    (net (code "94") (name "/U5_TX(C12)") (class "Default")
      (node (ref "P4") (pin "13") (pinfunction "13_13") (pintype "passive"))
      (node (ref "U1") (pin "113") (pinfunction "PC12/SPI3_MOSI/U3_CK/U5_TX/SDIO_CK/DCMI_D9/I2S3_SD_113") (pintype "passive"))
    )
    (net (code "95") (name "/U6_RX(G9)") (class "Default")
      (node (ref "P4") (pin "15") (pinfunction "15_15") (pintype "passive"))
      (node (ref "U1") (pin "124") (pinfunction "PG9/FSMC_NE2/FSMC_NCE3/U6_RX_124") (pintype "passive"))
    )
    (net (code "96") (name "/U6_TX(G14)") (class "Default")
      (node (ref "P4") (pin "5") (pinfunction "5_5") (pintype "passive"))
      (node (ref "U1") (pin "129") (pinfunction "PG14/FSMC_A25/U6_TX/ETH_MII_TXD1/ETH_RMII_TXD1_129") (pintype "passive"))
    )
    (net (code "97") (name "/VBAT") (class "Default")
      (node (ref "U1") (pin "6") (pinfunction "VBAT_6") (pintype "passive"))
    )
    (net (code "98") (name "/VDDA") (class "Default")
      (node (ref "C11") (pin "2") (pinfunction "2_2") (pintype "passive"))
      (node (ref "C12") (pin "2") (pinfunction "2_2") (pintype "passive"))
      (node (ref "R3") (pin "1") (pinfunction "1_1") (pintype "passive"))
      (node (ref "U1") (pin "32") (pinfunction "Vref+_32") (pintype "passive"))
      (node (ref "U1") (pin "33") (pinfunction "VDDA_33") (pintype "passive"))
    )
    (net (code "99") (name "/WiFi_ANT") (class "Default")
      (node (ref "C13") (pin "2") (pinfunction "2_2") (pintype "passive"))
      (node (ref "C22") (pin "2") (pinfunction "2_2") (pintype "passive"))
      (node (ref "U7") (pin "17") (pinfunction "ANT_2.4G_17") (pintype "passive"))
    )
    (net (code "100") (name "/WiFi_Linked") (class "Default")
      (node (ref "LED2") (pin "2") (pinfunction "2_2") (pintype "passive"))
      (node (ref "R13") (pin "1") (pinfunction "1_1") (pintype "passive"))
      (node (ref "U7") (pin "13") (pinfunction "nLink_13") (pintype "passive"))
    )
    (net (code "101") (name "/WiFi_Reload") (class "Default")
      (node (ref "K1") (pin "2") (pinfunction "2_2") (pintype "passive"))
      (node (ref "R14") (pin "1") (pinfunction "1_1") (pintype "passive"))
      (node (ref "U7") (pin "12") (pinfunction "nReload_12") (pintype "passive"))
    )
    (net (code "102") (name "/WiFi_Reload(C10)") (class "Default")
      (node (ref "U1") (pin "111") (pinfunction "PC10/SPI3_SCK/U3_TX/U4_TX/SDIO_D2/DCMI_D8/I2S3_CK_111") (pintype "passive"))
    )
    (net (code "103") (name "/WiFi_Reload(E15)") (class "Default")
      (node (ref "R14") (pin "2") (pinfunction "2_2") (pintype "passive"))
      (node (ref "U1") (pin "68") (pinfunction "PE15/FSMC_D12/TIM1_BKIN_68") (pintype "passive"))
    )
    (net (code "104") (name "/Wifi_Connect(D11)") (class "Default")
      (node (ref "R13") (pin "2") (pinfunction "2_2") (pintype "passive"))
      (node (ref "U1") (pin "80") (pinfunction "PD11/FSMC_A16/FSMC_CLE/U3_CTS_80") (pintype "passive"))
    )
    (net (code "105") (name "3.3V") (class "Default")
      (node (ref "B1") (pin "1") (pinfunction "P_1") (pintype "passive"))
      (node (ref "C14") (pin "2") (pinfunction "2_2") (pintype "passive"))
      (node (ref "C15") (pin "2") (pinfunction "2_2") (pintype "passive"))
      (node (ref "C16") (pin "2") (pinfunction "2_2") (pintype "passive"))
      (node (ref "C17") (pin "2") (pinfunction "2_2") (pintype "passive"))
      (node (ref "C18") (pin "2") (pinfunction "2_2") (pintype "passive"))
      (node (ref "C19") (pin "2") (pinfunction "2_2") (pintype "passive"))
      (node (ref "C20") (pin "2") (pinfunction "2_2") (pintype "passive"))
      (node (ref "C21") (pin "2") (pinfunction "2_2") (pintype "passive"))
      (node (ref "C26") (pin "1") (pinfunction "1_1") (pintype "passive"))
      (node (ref "C3") (pin "1") (pinfunction "1_1") (pintype "passive"))
      (node (ref "C4") (pin "2") (pinfunction "2_2") (pintype "passive"))
      (node (ref "C8") (pin "1") (pinfunction "1_1") (pintype "passive"))
      (node (ref "D1") (pin "2") (pinfunction "2_2") (pintype "passive"))
      (node (ref "LED1") (pin "1") (pintype "passive"))
      (node (ref "P1") (pin "1") (pinfunction "1_1") (pintype "passive"))
      (node (ref "P3") (pin "2") (pinfunction "2_2") (pintype "passive"))
      (node (ref "P4") (pin "18") (pinfunction "18_18") (pintype "passive"))
      (node (ref "P6") (pin "11") (pinfunction "11_11") (pintype "passive"))
      (node (ref "P9") (pin "1") (pinfunction "1_1") (pintype "passive"))
      (node (ref "R11") (pin "2") (pinfunction "2_2") (pintype "passive"))
      (node (ref "R12") (pin "1") (pinfunction "1_1") (pintype "passive"))
      (node (ref "R15") (pin "1") (pinfunction "1_1") (pintype "passive"))
      (node (ref "R16") (pin "1") (pinfunction "1_1") (pintype "passive"))
      (node (ref "R2") (pin "2") (pinfunction "2_2") (pintype "passive"))
      (node (ref "R2") (pin "4") (pinfunction "4_4") (pintype "passive"))
      (node (ref "R3") (pin "2") (pinfunction "2_2") (pintype "passive"))
      (node (ref "R4") (pin "2") (pinfunction "2_2") (pintype "passive"))
      (node (ref "R5") (pin "1") (pinfunction "1_1") (pintype "passive"))
      (node (ref "R7") (pin "2") (pinfunction "2_2") (pintype "passive"))
      (node (ref "U1") (pin "108") (pinfunction "VDD_108") (pintype "passive"))
      (node (ref "U1") (pin "121") (pinfunction "VDD_121") (pintype "passive"))
      (node (ref "U1") (pin "131") (pinfunction "VDD_131") (pintype "passive"))
      (node (ref "U1") (pin "144") (pinfunction "VDD_144") (pintype "passive"))
      (node (ref "U1") (pin "17") (pinfunction "VDD_17") (pintype "passive"))
      (node (ref "U1") (pin "30") (pinfunction "VDD_30") (pintype "passive"))
      (node (ref "U1") (pin "39") (pinfunction "VDD_39") (pintype "passive"))
      (node (ref "U1") (pin "52") (pinfunction "VDD_52") (pintype "passive"))
      (node (ref "U1") (pin "62") (pinfunction "VDD_62") (pintype "passive"))
      (node (ref "U1") (pin "72") (pinfunction "VDD_72") (pintype "passive"))
      (node (ref "U1") (pin "84") (pinfunction "VDD_84") (pintype "passive"))
      (node (ref "U1") (pin "95") (pinfunction "VDD_95") (pintype "passive"))
      (node (ref "U2") (pin "2") (pinfunction "OUT_2") (pintype "passive"))
      (node (ref "U2") (pin "4") (pinfunction "OUT_4") (pintype "passive"))
      (node (ref "U5") (pin "11") (pinfunction "VCC_11") (pintype "passive"))
      (node (ref "U5") (pin "2") (pinfunction "VCC_2") (pintype "passive"))
      (node (ref "U6") (pin "3") (pinfunction "~{WP}_3") (pintype "passive"))
      (node (ref "U6") (pin "7") (pinfunction "~{RESET}_7") (pintype "passive"))
      (node (ref "U6") (pin "8") (pinfunction "VCC_8") (pintype "passive"))
      (node (ref "U7") (pin "15") (pinfunction "DVDD_15") (pintype "passive"))
      (node (ref "U8") (pin "2") (pinfunction "2_2") (pintype "passive"))
    )
    (net (code "106") (name "5.0V") (class "Default")
      (node (ref "C1") (pin "1") (pinfunction "1_1") (pintype "passive"))
      (node (ref "C2") (pin "2") (pinfunction "2_2") (pintype "passive"))
      (node (ref "C5") (pin "1") (pinfunction "1_1") (pintype "passive"))
      (node (ref "C6") (pin "1") (pinfunction "1_1") (pintype "passive"))
      (node (ref "F1") (pin "2") (pinfunction "2_2") (pintype "passive"))
      (node (ref "P7") (pin "1") (pinfunction "1_1") (pintype "passive"))
      (node (ref "R2") (pin "6") (pinfunction "6_6") (pintype "passive"))
      (node (ref "U2") (pin "3") (pinfunction "IN_3") (pintype "passive"))
      (node (ref "U3") (pin "7") (pinfunction "REG_7") (pintype "passive"))
      (node (ref "U3") (pin "8") (pinfunction "VBUS_8") (pintype "passive"))
    )
    (net (code "107") (name "GND") (class "Default")
      (node (ref "C1") (pin "2") (pinfunction "2_2") (pintype "passive"))
      (node (ref "C10") (pin "1") (pinfunction "1_1") (pintype "passive"))
      (node (ref "C11") (pin "1") (pinfunction "1_1") (pintype "passive"))
      (node (ref "C12") (pin "1") (pinfunction "1_1") (pintype "passive"))
      (node (ref "C14") (pin "1") (pinfunction "1_1") (pintype "passive"))
      (node (ref "C15") (pin "1") (pinfunction "1_1") (pintype "passive"))
      (node (ref "C16") (pin "1") (pinfunction "1_1") (pintype "passive"))
      (node (ref "C17") (pin "1") (pinfunction "1_1") (pintype "passive"))
      (node (ref "C18") (pin "1") (pinfunction "1_1") (pintype "passive"))
      (node (ref "C19") (pin "1") (pinfunction "1_1") (pintype "passive"))
      (node (ref "C2") (pin "1") (pinfunction "1_1") (pintype "passive"))
      (node (ref "C20") (pin "1") (pinfunction "1_1") (pintype "passive"))
      (node (ref "C21") (pin "1") (pinfunction "1_1") (pintype "passive"))
      (node (ref "C22") (pin "1") (pinfunction "1_1") (pintype "passive"))
      (node (ref "C23") (pin "1") (pinfunction "1_1") (pintype "passive"))
      (node (ref "C24") (pin "2") (pinfunction "2_2") (pintype "passive"))
      (node (ref "C25") (pin "2") (pinfunction "2_2") (pintype "passive"))
      (node (ref "C26") (pin "2") (pinfunction "2_2") (pintype "passive"))
      (node (ref "C3") (pin "2") (pinfunction "2_2") (pintype "passive"))
      (node (ref "C4") (pin "1") (pinfunction "1_1") (pintype "passive"))
      (node (ref "C5") (pin "2") (pinfunction "2_2") (pintype "passive"))
      (node (ref "C6") (pin "2") (pinfunction "2_2") (pintype "passive"))
      (node (ref "C7") (pin "2") (pinfunction "2_2") (pintype "passive"))
      (node (ref "C8") (pin "2") (pinfunction "2_2") (pintype "passive"))
      (node (ref "C9") (pin "1") (pinfunction "1_1") (pintype "passive"))
      (node (ref "D1") (pin "1") (pintype "passive"))
      (node (ref "J1") (pin "2") (pinfunction "GND_2") (pintype "passive"))
      (node (ref "J1") (pin "3") (pinfunction "GND_3") (pintype "passive"))
      (node (ref "K1") (pin "1") (pinfunction "1_1") (pintype "passive"))
      (node (ref "K2") (pin "2") (pinfunction "2_2") (pintype "passive"))
      (node (ref "K3") (pin "2") (pinfunction "2_2") (pintype "passive"))
      (node (ref "P1") (pin "4") (pinfunction "4_4") (pintype "passive"))
      (node (ref "P2") (pin "5") (pinfunction "B4_5") (pintype "passive"))
      (node (ref "P2") (pin "6") (pinfunction "B3_6") (pintype "passive"))
      (node (ref "P2") (pin "7") (pinfunction "B2_7") (pintype "passive"))
      (node (ref "P2") (pin "8") (pinfunction "B1_8") (pintype "passive"))
      (node (ref "P3") (pin "1") (pinfunction "1_1") (pintype "passive"))
      (node (ref "P3") (pin "7") (pinfunction "7_7") (pintype "passive"))
      (node (ref "P4") (pin "2") (pinfunction "2_2") (pintype "passive"))
      (node (ref "P4") (pin "3") (pinfunction "3_3") (pintype "passive"))
      (node (ref "P6") (pin "10") (pinfunction "10_10") (pintype "passive"))
      (node (ref "P6") (pin "20") (pinfunction "20_20") (pintype "passive"))
      (node (ref "P7") (pin "2") (pinfunction "2_2") (pintype "passive"))
      (node (ref "P9") (pin "2") (pinfunction "2_2") (pintype "passive"))
      (node (ref "Q1") (pin "2") (pinfunction "E_2") (pintype "passive"))
      (node (ref "R1") (pin "1") (pinfunction "1_1") (pintype "passive"))
      (node (ref "R10") (pin "2") (pinfunction "2_2") (pintype "passive"))
      (node (ref "R2") (pin "8") (pinfunction "8_8") (pintype "passive"))
      (node (ref "R6") (pin "2") (pinfunction "2_2") (pintype "passive"))
      (node (ref "U1") (pin "107") (pinfunction "VSS_107") (pintype "passive"))
      (node (ref "U1") (pin "120") (pinfunction "VSS_120") (pintype "passive"))
      (node (ref "U1") (pin "130") (pinfunction "VSS_130") (pintype "passive"))
      (node (ref "U1") (pin "16") (pinfunction "VSS_16") (pintype "passive"))
      (node (ref "U1") (pin "31") (pinfunction "VSSA_31") (pintype "passive"))
      (node (ref "U1") (pin "38") (pinfunction "VSS_38") (pintype "passive"))
      (node (ref "U1") (pin "51") (pinfunction "VSS_51") (pintype "passive"))
      (node (ref "U1") (pin "61") (pinfunction "VSS_61") (pintype "passive"))
      (node (ref "U1") (pin "83") (pinfunction "VSS_83") (pintype "passive"))
      (node (ref "U1") (pin "94") (pinfunction "VSS_94") (pintype "passive"))
      (node (ref "U2") (pin "1") (pinfunction "GND_1") (pintype "passive"))
      (node (ref "U3") (pin "3") (pinfunction "GND_3") (pintype "passive"))
      (node (ref "U4") (pin "5") (pinfunction "GND_5") (pintype "power_in"))
      (node (ref "U5") (pin "5") (pinfunction "GND_5") (pintype "passive"))
      (node (ref "U5") (pin "8") (pinfunction "GND_8") (pintype "passive"))
      (node (ref "U6") (pin "4") (pinfunction "GND_4") (pintype "passive"))
      (node (ref "U7") (pin "16") (pinfunction "GND_16") (pintype "passive"))
      (node (ref "X1") (pin "3") (pinfunction "3_3") (pintype "passive"))
    )
    (net (code "108") (name "Net-(B1-G)") (class "Default")
      (node (ref "B1") (pin "2") (pinfunction "G_2") (pintype "passive"))
      (node (ref "Q1") (pin "3") (pinfunction "C_3") (pintype "passive"))
    )
    (net (code "109") (name "Net-(J1-ANT)") (class "Default")
      (node (ref "C13") (pin "1") (pinfunction "1_1") (pintype "passive"))
      (node (ref "C23") (pin "2") (pinfunction "2_2") (pintype "passive"))
      (node (ref "J1") (pin "1") (pinfunction "ANT_1") (pintype "passive"))
    )
    (net (code "110") (name "Net-(LED1-Pad2)") (class "Default")
      (node (ref "LED1") (pin "2") (pinfunction "2_2") (pintype "passive"))
      (node (ref "R1") (pin "2") (pinfunction "2_2") (pintype "passive"))
    )
    (net (code "111") (name "Net-(LED2-Pad1)") (class "Default")
      (node (ref "LED2") (pin "1") (pintype "passive"))
      (node (ref "R5") (pin "2") (pinfunction "2_2") (pintype "passive"))
    )
    (net (code "112") (name "Net-(Q1-B)") (class "Default")
      (node (ref "Q1") (pin "1") (pinfunction "B_1") (pintype "passive"))
      (node (ref "R8") (pin "7") (pinfunction "7_7") (pintype "passive"))
    )
    (net (code "113") (name "Net-(U1-PDR_ON)") (class "Default")
      (node (ref "R4") (pin "1") (pinfunction "1_1") (pintype "passive"))
      (node (ref "U1") (pin "143") (pinfunction "PDR_ON_143") (pintype "passive"))
    )
    (net (code "114") (name "Net-(U1-Vcap_1)") (class "Default")
      (node (ref "C9") (pin "2") (pinfunction "2_2") (pintype "passive"))
      (node (ref "U1") (pin "71") (pinfunction "Vcap_1_71") (pintype "passive"))
    )
    (net (code "115") (name "Net-(U1-Vcap_2)") (class "Default")
      (node (ref "C10") (pin "2") (pinfunction "2_2") (pintype "passive"))
      (node (ref "U1") (pin "106") (pinfunction "Vcap_2_106") (pintype "passive"))
    )
    (net (code "116") (name "Net-(U3-VDD)") (class "Default")
      (node (ref "C7") (pin "1") (pinfunction "1_1") (pintype "passive"))
      (node (ref "U3") (pin "6") (pinfunction "VDD_6") (pintype "passive"))
    )
    (net (code "117") (name "Net-(U8-B)") (class "Default")
      (node (ref "R8") (pin "1") (pinfunction "1_1") (pintype "passive"))
      (node (ref "U8") (pin "1") (pinfunction "B_1") (pintype "passive"))
    )
    (net (code "118") (name "Net-(U8-G)") (class "Default")
      (node (ref "R8") (pin "3") (pinfunction "3_3") (pintype "passive"))
      (node (ref "U8") (pin "3") (pinfunction "G_3") (pintype "passive"))
    )
    (net (code "119") (name "Net-(U8-R)") (class "Default")
      (node (ref "R8") (pin "5") (pinfunction "5_5") (pintype "passive"))
      (node (ref "U8") (pin "4") (pinfunction "R_4") (pintype "passive"))
    )
    (net (code "120") (name "POWER_5V_IN") (class "Default")
      (node (ref "F1") (pin "1") (pinfunction "1_1") (pintype "passive"))
      (node (ref "P4") (pin "19") (pinfunction "19_19") (pintype "passive"))
      (node (ref "U4") (pin "1") (pinfunction "VCC_1") (pintype "power_in"))
    )
    (net (code "121") (name "unconnected-(U1-PA12{slash}TIM1_ETR{slash}U1_RTS{slash}CAN1_TX{slash}OTG_FS_DP-Pad104)") (class "Default")
      (node (ref "U1") (pin "104") (pinfunction "PA12/TIM1_ETR/U1_RTS/CAN1_TX/OTG_FS_DP_104") (pintype "passive"))
    )
    (net (code "122") (name "unconnected-(U1-PC13{slash}RTC_AF1-Pad7)") (class "Default")
      (node (ref "U1") (pin "7") (pinfunction "PC13/RTC_AF1_7") (pintype "passive+no_connect"))
    )
    (net (code "123") (name "unconnected-(U1-PC14-OSC32_IN-Pad8)") (class "Default")
      (node (ref "U1") (pin "8") (pinfunction "PC14-OSC32_IN_8") (pintype "passive+no_connect"))
    )
    (net (code "124") (name "unconnected-(U1-PC15-OSC32_OUT-Pad9)") (class "Default")
      (node (ref "U1") (pin "9") (pinfunction "PC15-OSC32_OUT_9") (pintype "passive+no_connect"))
    )
    (net (code "125") (name "unconnected-(U1-PD5{slash}FSMC_NWE{slash}U2_TX-Pad119)") (class "Default")
      (node (ref "U1") (pin "119") (pinfunction "PD5/FSMC_NWE/U2_TX_119") (pintype "passive+no_connect"))
    )
    (net (code "126") (name "unconnected-(U1-PE4{slash}TRACED1{slash}FSMC_A20{slash}DCMI_D4-Pad3)") (class "Default")
      (node (ref "U1") (pin "3") (pinfunction "PE4/TRACED1/FSMC_A20/DCMI_D4_3") (pintype "passive"))
    )
    (net (code "127") (name "unconnected-(U1-PE7{slash}FSMC_D4{slash}TIM1_ETR-Pad58)") (class "Default")
      (node (ref "U1") (pin "58") (pinfunction "PE7/FSMC_D4/TIM1_ETR_58") (pintype "passive"))
    )
    (net (code "128") (name "unconnected-(U1-PF2{slash}FSMC_A2{slash}I2C2_SMBA-Pad12)") (class "Default")
      (node (ref "U1") (pin "12") (pinfunction "PF2/FSMC_A2/I2C2_SMBA_12") (pintype "passive"))
    )
    (net (code "129") (name "unconnected-(U1-PF10{slash}FSMC_INTR{slash}ADC3_IN8-Pad22)") (class "Default")
      (node (ref "U1") (pin "22") (pinfunction "PF10/FSMC_INTR/ADC3_IN8_22") (pintype "passive"))
    )
    (net (code "130") (name "unconnected-(U1-PF11{slash}DCMI_D12-Pad49)") (class "Default")
      (node (ref "U1") (pin "49") (pinfunction "PF11/DCMI_D12_49") (pintype "passive"))
    )
    (net (code "131") (name "unconnected-(U1-PF12{slash}FSMC_A6-Pad50)") (class "Default")
      (node (ref "U1") (pin "50") (pinfunction "PF12/FSMC_A6_50") (pintype "passive"))
    )
    (net (code "132") (name "unconnected-(U1-PF13{slash}FSMC_A7-Pad53)") (class "Default")
      (node (ref "U1") (pin "53") (pinfunction "PF13/FSMC_A7_53") (pintype "passive"))
    )
    (net (code "133") (name "unconnected-(U1-PF14{slash}FSMC_A8-Pad54)") (class "Default")
      (node (ref "U1") (pin "54") (pinfunction "PF14/FSMC_A8_54") (pintype "passive"))
    )
    (net (code "134") (name "unconnected-(U1-PF15{slash}FSMC_A9-Pad55)") (class "Default")
      (node (ref "U1") (pin "55") (pinfunction "PF15/FSMC_A9_55") (pintype "passive"))
    )
    (net (code "135") (name "unconnected-(U1-PG0{slash}FSMC_A10-Pad56)") (class "Default")
      (node (ref "U1") (pin "56") (pinfunction "PG0/FSMC_A10_56") (pintype "passive"))
    )
    (net (code "136") (name "unconnected-(U1-PG1{slash}FSMC_A11-Pad57)") (class "Default")
      (node (ref "U1") (pin "57") (pinfunction "PG1/FSMC_A11_57") (pintype "passive"))
    )
    (net (code "137") (name "unconnected-(U1-PG2{slash}FSMC_A12-Pad87)") (class "Default")
      (node (ref "U1") (pin "87") (pinfunction "PG2/FSMC_A12_87") (pintype "passive"))
    )
    (net (code "138") (name "unconnected-(U1-PG4{slash}FSMC_A14-Pad89)") (class "Default")
      (node (ref "U1") (pin "89") (pinfunction "PG4/FSMC_A14_89") (pintype "passive"))
    )
    (net (code "139") (name "unconnected-(U1-PG5{slash}FSMC_A15-Pad90)") (class "Default")
      (node (ref "U1") (pin "90") (pinfunction "PG5/FSMC_A15_90") (pintype "passive"))
    )
    (net (code "140") (name "unconnected-(U1-PG6{slash}FSMC_INT2-Pad91)") (class "Default")
      (node (ref "U1") (pin "91") (pinfunction "PG6/FSMC_INT2_91") (pintype "passive"))
    )
    (net (code "141") (name "unconnected-(U1-PG7{slash}FSMC_INT3{slash}U6_CK-Pad92)") (class "Default")
      (node (ref "U1") (pin "92") (pinfunction "PG7/FSMC_INT3/U6_CK_92") (pintype "passive"))
    )
    (net (code "142") (name "unconnected-(U1-PG8{slash}U6_RTS{slash}ETH_PPS_OUT-Pad93)") (class "Default")
      (node (ref "U1") (pin "93") (pinfunction "PG8/U6_RTS/ETH_PPS_OUT_93") (pintype "passive"))
    )
    (net (code "143") (name "unconnected-(U1-PG15{slash}U6_CTS{slash}DCMI_D13-Pad132)") (class "Default")
      (node (ref "U1") (pin "132") (pinfunction "PG15/U6_CTS/DCMI_D13_132") (pintype "passive"))
    )
    (net (code "144") (name "unconnected-(U3-CTS-Pad23)") (class "Default")
      (node (ref "U3") (pin "23") (pinfunction "CTS_23") (pintype "passive+no_connect"))
    )
    (net (code "145") (name "unconnected-(U3-DCO-Pad1)") (class "Default")
      (node (ref "U3") (pin "1") (pinfunction "DCO_1") (pintype "passive+no_connect"))
    )
    (net (code "146") (name "unconnected-(U3-DSR-Pad27)") (class "Default")
      (node (ref "U3") (pin "27") (pinfunction "DSR_27") (pintype "passive+no_connect"))
    )
    (net (code "147") (name "unconnected-(U3-DTR-Pad28)") (class "Default")
      (node (ref "U3") (pin "28") (pinfunction "DTR_28") (pintype "passive+no_connect"))
    )
    (net (code "148") (name "unconnected-(U3-NC-Pad10)") (class "Default")
      (node (ref "U3") (pin "10") (pinfunction "NC_10") (pintype "passive+no_connect"))
    )
    (net (code "149") (name "unconnected-(U3-NC-Pad13)") (class "Default")
      (node (ref "U3") (pin "13") (pinfunction "NC_13") (pintype "passive+no_connect"))
    )
    (net (code "150") (name "unconnected-(U3-NC-Pad14)") (class "Default")
      (node (ref "U3") (pin "14") (pinfunction "NC_14") (pintype "passive+no_connect"))
    )
    (net (code "151") (name "unconnected-(U3-NC-Pad15)") (class "Default")
      (node (ref "U3") (pin "15") (pinfunction "NC_15") (pintype "passive+no_connect"))
    )
    (net (code "152") (name "unconnected-(U3-NC-Pad16)") (class "Default")
      (node (ref "U3") (pin "16") (pinfunction "NC_16") (pintype "passive+no_connect"))
    )
    (net (code "153") (name "unconnected-(U3-NC-Pad17)") (class "Default")
      (node (ref "U3") (pin "17") (pinfunction "NC_17") (pintype "passive+no_connect"))
    )
    (net (code "154") (name "unconnected-(U3-NC-Pad19)") (class "Default")
      (node (ref "U3") (pin "19") (pinfunction "NC_19") (pintype "passive+no_connect"))
    )
    (net (code "155") (name "unconnected-(U3-NC-Pad20)") (class "Default")
      (node (ref "U3") (pin "20") (pinfunction "NC_20") (pintype "passive+no_connect"))
    )
    (net (code "156") (name "unconnected-(U3-NC-Pad21)") (class "Default")
      (node (ref "U3") (pin "21") (pinfunction "NC_21") (pintype "passive+no_connect"))
    )
    (net (code "157") (name "unconnected-(U3-NC-Pad22)") (class "Default")
      (node (ref "U3") (pin "22") (pinfunction "NC_22") (pintype "passive+no_connect"))
    )
    (net (code "158") (name "unconnected-(U3-RI-Pad2)") (class "Default")
      (node (ref "U3") (pin "2") (pinfunction "RI_2") (pintype "passive+no_connect"))
    )
    (net (code "159") (name "unconnected-(U3-RTS-Pad24)") (class "Default")
      (node (ref "U3") (pin "24") (pinfunction "RTS_24") (pintype "passive+no_connect"))
    )
    (net (code "160") (name "unconnected-(U3-SUS-Pad12)") (class "Default")
      (node (ref "U3") (pin "12") (pinfunction "SUS_12") (pintype "passive+no_connect"))
    )
    (net (code "161") (name "unconnected-(U3-VPP-Pad18)") (class "Default")
      (node (ref "U3") (pin "18") (pinfunction "VPP_18") (pintype "passive+no_connect"))
    )
    (net (code "162") (name "unconnected-(U4-ID-Pad4)") (class "Default")
      (node (ref "U4") (pin "4") (pinfunction "ID_4") (pintype "power_in"))
    )
    (net (code "163") (name "unconnected-(U5-D0-Pad1)") (class "Default")
      (node (ref "U5") (pin "1") (pinfunction "D0_1") (pintype "passive"))
    )
    (net (code "164") (name "unconnected-(U5-D1-Pad6)") (class "Default")
      (node (ref "U5") (pin "6") (pinfunction "D1_6") (pintype "passive"))
    )
    (net (code "165") (name "unconnected-(U5-D2-Pad12)") (class "Default")
      (node (ref "U5") (pin "12") (pinfunction "D2_12") (pintype "passive"))
    )
    (net (code "166") (name "unconnected-(U5-D3-Pad7)") (class "Default")
      (node (ref "U5") (pin "7") (pinfunction "D3_7") (pintype "passive"))
    )
    (net (code "167") (name "unconnected-(U7-GPIO1-Pad1)") (class "Default")
      (node (ref "U7") (pin "1") (pinfunction "GPIO1_1") (pintype "passive"))
    )
    (net (code "168") (name "unconnected-(U7-GPIO2-Pad2)") (class "Default")
      (node (ref "U7") (pin "2") (pinfunction "GPIO2_2") (pintype "passive"))
    )
    (net (code "169") (name "unconnected-(U7-GPIO3-Pad3)") (class "Default")
      (node (ref "U7") (pin "3") (pinfunction "GPIO3_3") (pintype "passive"))
    )
    (net (code "170") (name "unconnected-(U7-GPIO4-Pad4)") (class "Default")
      (node (ref "U7") (pin "4") (pinfunction "GPIO4_4") (pintype "passive"))
    )
    (net (code "171") (name "unconnected-(U7-UART0_CTS-Pad7)") (class "Default")
      (node (ref "U7") (pin "7") (pinfunction "UART0_CTS_7") (pintype "passive"))
    )
    (net (code "172") (name "unconnected-(U7-UART0_RTS-Pad8)") (class "Default")
      (node (ref "U7") (pin "8") (pinfunction "UART0_RTS_8") (pintype "passive"))
    )
    (net (code "173") (name "unconnected-(U7-WPS-Pad9)") (class "Default")
      (node (ref "U7") (pin "9") (pinfunction "WPS_9") (pintype "passive"))
    )
    (net (code "174") (name "unconnected-(U7-WPS-Pad14)") (class "Default")
      (node (ref "U7") (pin "14") (pinfunction "WPS_14") (pintype "passive"))
    )
    (net (code "175") (name "unconnected-(U7-nReady-Pad11)") (class "Default")
      (node (ref "U7") (pin "11") (pinfunction "nReady_11") (pintype "passive"))
    )
    (net (code "176") (name "unconnected-(U7-nReset-Pad10)") (class "Default")
      (node (ref "U7") (pin "10") (pinfunction "nReset_10") (pintype "passive"))
    )
  )
)
